# Pag3_Front_end_adc_dac.net
KiCad netlist of a schematic drawn in Altium Designer
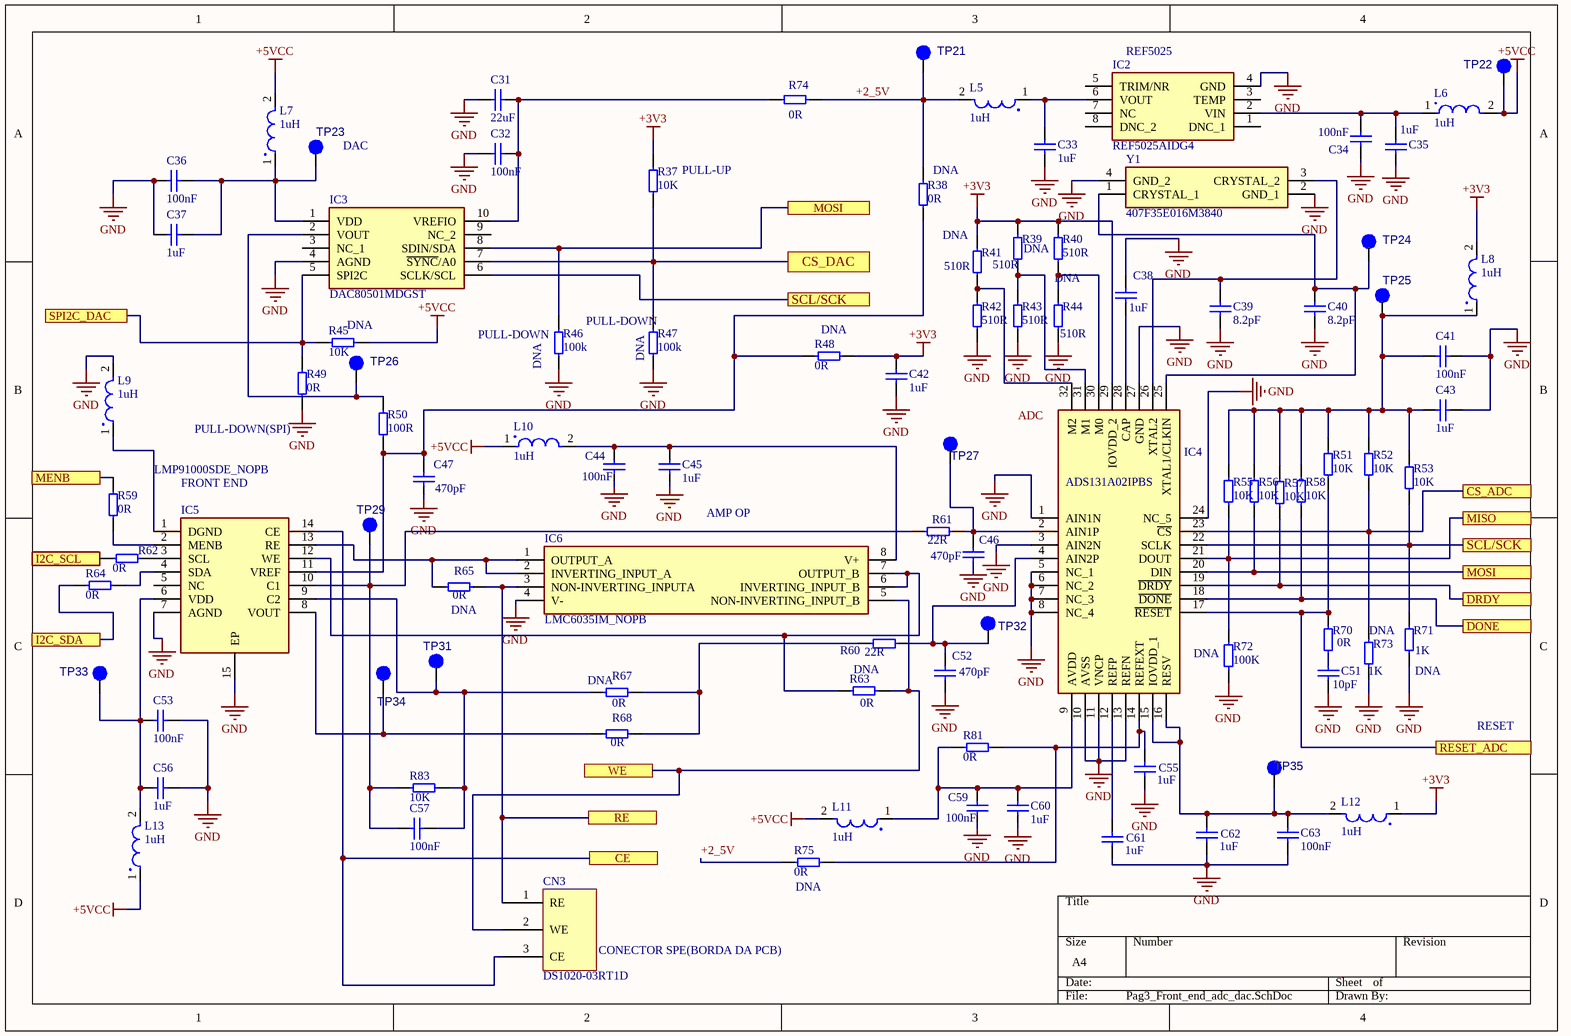
[diagram p0: Pag3_Front_end_adc_dac.SchDoc]

(export (version "E")
  (design (tool "Eeschema 10.0.6"))
  (components
    (comp (ref "C31")
      (value "22uF")
      (footprint "0603")
      (description "Multilayer Ceramic Capacitors MLCC - SMD/SMT 22uF 0603 6.3V 20%")
      (fields (field (name "MANUFACTURER") "KEMET") (field (name "MPN") "C0603C226M9PACTU"))
      (libsource (lib "potenciostato") (part "CAP_10uF_10V"))
    )
    (comp (ref "C32")
      (value "100nF")
      (footprint "0603")
      (description "Multilayer Ceramic Capacitors MLCC - SMD/SMT 100nF 16V 0603 10%")
      (fields (field (name "MPN") "C0603C104K4RACTU") (field (name "MANUFACTURER") "Kemet"))
      (libsource (lib "potenciostato") (part "Cap_1"))
    )
    (comp (ref "C33")
      (value "1uF")
      (footprint "0603")
      (description "Multilayer Ceramic Capacitors MLCC - SMD/SMT 1uF 25V 0603 10%")
      (fields
        (field (name "MANUFACTURER") "Samsung Electro-Mechanics")
        (field (name "MPN") "CL10A105KA8NNNC")
      )
      (libsource (lib "potenciostato") (part "CAP_1uF"))
    )
    (comp (ref "C34")
      (value "100nF")
      (footprint "0603")
      (description "Multilayer Ceramic Capacitors MLCC - SMD/SMT 100nF 16V 0603 10%")
      (fields (field (name "MPN") "C0603C104K4RACTU") (field (name "MANUFACTURER") "Kemet"))
      (libsource (lib "potenciostato") (part "Cap_1"))
    )
    (comp (ref "C35")
      (value "1uF")
      (footprint "0603")
      (description "Multilayer Ceramic Capacitors MLCC - SMD/SMT 1uF 25V 0603 10%")
      (fields
        (field (name "MANUFACTURER") "Samsung Electro-Mechanics")
        (field (name "MPN") "CL10A105KA8NNNC")
      )
      (libsource (lib "potenciostato") (part "CAP_1uF"))
    )
    (comp (ref "C36")
      (value "100nF")
      (footprint "0603")
      (description "Multilayer Ceramic Capacitors MLCC - SMD/SMT 100nF 16V 0603 10%")
      (fields (field (name "MPN") "C0603C104K4RACTU") (field (name "MANUFACTURER") "Kemet"))
      (libsource (lib "potenciostato") (part "Cap_1"))
    )
    (comp (ref "C37")
      (value "1uF")
      (footprint "0603")
      (description "Multilayer Ceramic Capacitors MLCC - SMD/SMT 1uF 25V 0603 10%")
      (fields
        (field (name "MANUFACTURER") "Samsung Electro-Mechanics")
        (field (name "MPN") "CL10A105KA8NNNC")
      )
      (libsource (lib "potenciostato") (part "CAP_1uF"))
    )
    (comp (ref "C38")
      (value "1uF")
      (footprint "0603")
      (description "Multilayer Ceramic Capacitors MLCC - SMD/SMT 1uF 25V 0603 10%")
      (fields
        (field (name "MANUFACTURER") "Samsung Electro-Mechanics")
        (field (name "MPN") "CL10A105KA8NNNC")
      )
      (libsource (lib "potenciostato") (part "CAP_1uF"))
    )
    (comp (ref "C39")
      (value "8.2pF")
      (footprint "0603")
      (description "Multilayer Ceramic Capacitors MLCC - SMD/SMT 8.2pF 0603 16V 0.25pF")
      (fields (field (name "MPN") "C0603C829C4GACAUTO") (field (name "MANUFACTURER") "Kemet"))
      (libsource (lib "potenciostato") (part "Cap_1_1"))
    )
    (comp (ref "C40")
      (value "8.2pF")
      (footprint "0603")
      (description "Multilayer Ceramic Capacitors MLCC - SMD/SMT 8.2pF 0603 16V 0.25pF")
      (fields (field (name "MPN") "C0603C829C4GACAUTO") (field (name "MANUFACTURER") "Kemet"))
      (libsource (lib "potenciostato") (part "Cap_1_1"))
    )
    (comp (ref "C41")
      (value "100nF")
      (footprint "0603")
      (description "Multilayer Ceramic Capacitors MLCC - SMD/SMT 100nF 16V 0603 10%")
      (fields (field (name "MPN") "C0603C104K4RACTU") (field (name "MANUFACTURER") "Kemet"))
      (libsource (lib "potenciostato") (part "Cap_1"))
    )
    (comp (ref "C42")
      (value "1uF")
      (footprint "0603")
      (description "Multilayer Ceramic Capacitors MLCC - SMD/SMT 1uF 25V 0603 10%")
      (fields
        (field (name "MANUFACTURER") "Samsung Electro-Mechanics")
        (field (name "MPN") "CL10A105KA8NNNC")
      )
      (libsource (lib "potenciostato") (part "CAP_1uF"))
    )
    (comp (ref "C43")
      (value "1uF")
      (footprint "0603")
      (description "Multilayer Ceramic Capacitors MLCC - SMD/SMT 1uF 25V 0603 10%")
      (fields
        (field (name "MANUFACTURER") "Samsung Electro-Mechanics")
        (field (name "MPN") "CL10A105KA8NNNC")
      )
      (libsource (lib "potenciostato") (part "CAP_1uF"))
    )
    (comp (ref "C44")
      (value "100nF")
      (footprint "0603")
      (description "Multilayer Ceramic Capacitors MLCC - SMD/SMT 100nF 16V 0603 10%")
      (fields (field (name "MPN") "C0603C104K4RACTU") (field (name "MANUFACTURER") "Kemet"))
      (libsource (lib "potenciostato") (part "Cap_1"))
    )
    (comp (ref "C45")
      (value "1uF")
      (footprint "0603")
      (description "Multilayer Ceramic Capacitors MLCC - SMD/SMT 1uF 25V 0603 10%")
      (fields
        (field (name "MANUFACTURER") "Samsung Electro-Mechanics")
        (field (name "MPN") "CL10A105KA8NNNC")
      )
      (libsource (lib "") (part "CAP_1uF_1"))
    )
    (comp (ref "C46")
      (value "470pF")
      (footprint "0603")
      (description "Multilayer Ceramic Capacitors MLCC - SMD/SMT 470pF 0603 25V 5%")
      (fields (field (name "MANUFACTURER") "Kyocera AVX") (field (name "MPN") "06033A471JAT2A"))
      (libsource (lib "potenciostato") (part "CAP_100nF_10V"))
    )
    (comp (ref "C47")
      (value "470pF")
      (footprint "0603")
      (description "Multilayer Ceramic Capacitors MLCC - SMD/SMT 470pF 0603 25V 5%")
      (fields (field (name "MANUFACTURER") "Kyocera AVX") (field (name "MPN") "06033A471JAT2A"))
      (libsource (lib "potenciostato") (part "CAP_100nF_10V"))
    )
    (comp (ref "C51")
      (value "10pF")
      (footprint "0603")
      (description "Multilayer Ceramic Capacitors MLCC - SMD/SMT 10pF 0603 16V 10%")
      (fields (field (name "MPN") "0603YD100KAT2A") (field (name "MANUFACTURER") "Kyocera AVX"))
      (libsource (lib "potenciostato") (part "Cap_1_1"))
    )
    (comp (ref "C52")
      (value "470pF")
      (footprint "0603")
      (description "Multilayer Ceramic Capacitors MLCC - SMD/SMT 470pF 0603 25V 5%")
      (fields (field (name "MANUFACTURER") "Kyocera AVX") (field (name "MPN") "06033A471JAT2A"))
      (libsource (lib "potenciostato") (part "CAP_100nF_10V"))
    )
    (comp (ref "C53")
      (value "100nF")
      (footprint "0603")
      (description "Multilayer Ceramic Capacitors MLCC - SMD/SMT 100nF 16V 0603 10%")
      (fields (field (name "MPN") "C0603C104K4RACTU") (field (name "MANUFACTURER") "Kemet"))
      (libsource (lib "potenciostato") (part "Cap_1"))
    )
    (comp (ref "C55")
      (value "1uF")
      (footprint "0603")
      (description "Multilayer Ceramic Capacitors MLCC - SMD/SMT 1uF 25V 0603 10%")
      (fields
        (field (name "MANUFACTURER") "Samsung Electro-Mechanics")
        (field (name "MPN") "CL10A105KA8NNNC")
      )
      (libsource (lib "potenciostato") (part "CAP_1uF"))
    )
    (comp (ref "C56")
      (value "1uF")
      (footprint "0603")
      (description "Multilayer Ceramic Capacitors MLCC - SMD/SMT 1uF 25V 0603 10%")
      (fields
        (field (name "MANUFACTURER") "Samsung Electro-Mechanics")
        (field (name "MPN") "CL10A105KA8NNNC")
      )
      (libsource (lib "potenciostato") (part "CAP_1uF"))
    )
    (comp (ref "C57")
      (value "100nF")
      (footprint "0603")
      (description "Multilayer Ceramic Capacitors MLCC - SMD/SMT 100nF 16V 0603 10%")
      (fields (field (name "MPN") "C0603C104K4RACTU") (field (name "MANUFACTURER") "Kemet"))
      (libsource (lib "potenciostato") (part "Cap_1"))
    )
    (comp (ref "C59")
      (value "100nF")
      (footprint "0603")
      (description "Multilayer Ceramic Capacitors MLCC - SMD/SMT 100nF 16V 0603 10%")
      (fields (field (name "MPN") "C0603C104K4RACTU") (field (name "MANUFACTURER") "Kemet"))
      (libsource (lib "potenciostato") (part "Cap_1"))
    )
    (comp (ref "C60")
      (value "1uF")
      (footprint "0603")
      (description "Multilayer Ceramic Capacitors MLCC - SMD/SMT 1uF 25V 0603 10%")
      (fields
        (field (name "MANUFACTURER") "Samsung Electro-Mechanics")
        (field (name "MPN") "CL10A105KA8NNNC")
      )
      (libsource (lib "potenciostato") (part "CAP_1uF"))
    )
    (comp (ref "C61")
      (value "1uF")
      (footprint "0603")
      (description "Multilayer Ceramic Capacitors MLCC - SMD/SMT 1uF 25V 0603 10%")
      (fields
        (field (name "MANUFACTURER") "Samsung Electro-Mechanics")
        (field (name "MPN") "CL10A105KA8NNNC")
      )
      (libsource (lib "potenciostato") (part "CAP_1uF"))
    )
    (comp (ref "C62")
      (value "1uF")
      (footprint "0603")
      (description "Multilayer Ceramic Capacitors MLCC - SMD/SMT 1uF 25V 0603 10%")
      (fields
        (field (name "MANUFACTURER") "Samsung Electro-Mechanics")
        (field (name "MPN") "CL10A105KA8NNNC")
      )
      (libsource (lib "potenciostato") (part "CAP_1uF"))
    )
    (comp (ref "C63")
      (value "100nF")
      (footprint "0603")
      (description "Multilayer Ceramic Capacitors MLCC - SMD/SMT 100nF 16V 0603 10%")
      (fields (field (name "MPN") "C0603C104K4RACTU") (field (name "MANUFACTURER") "Kemet"))
      (libsource (lib "potenciostato") (part "Cap_1"))
    )
    (comp (ref "CN3")
      (value "DS1020-03RT1D")
      (footprint "DS1020-03RT1D")
      (description "Connector: FFC/FPC; angled 90°; PIN: 3; Non-ZIF; THT; tinned; 20mΩ")
      (fields (field (name "MANUFACTURER") "Connfly"))
      (libsource (lib "DS1020-03RT1D") (part "DS1020-03RT1D"))
    )
    (comp (ref "IC2")
      (value "REF5025AIDG4")
      (footprint "SOIC127P600X175-8N")
      (description "Integrated Circuit")
      (fields (field (name "MANUFACTURER") "Texas Instruments"))
      (libsource (lib "ref5025") (part "REF5025AIDG4"))
    )
    (comp (ref "IC3")
      (value "DAC80501MDGST")
      (footprint "SOP50P490X110-10N")
      (description "Integrated Circuit")
      (fields (field (name "MANUFACTURER") "Texas Instruments"))
      (libsource (lib "dac80501") (part "DAC80501MDGST"))
    )
    (comp (ref "IC4")
      (value "ADS131A02IPBS")
      (footprint "QFP50P700X700X120-32N")
      (description "Integrated Circuit")
      (fields (field (name "MANUFACTURER") "Texas Instruments"))
      (libsource (lib "ADS131A02") (part "ADS131A02IPBS"))
    )
    (comp (ref "IC5")
      (value "LMP91000SDE_NOPB")
      (footprint "SON50P400X400X80-15N")
      (description "Integrated Circuit")
      (fields (field (name "MPN") "LMP91000SDE/NOPB") (field (name "MANUFACTURER") "Texas Instruments"))
      (libsource (lib "LMP91000") (part "LMP91000SDE_NOPB"))
    )
    (comp (ref "IC6")
      (value "LMC6035IM_NOPB")
      (footprint "SOIC127P600X175-8N")
      (description "Integrated Circuit")
      (fields (field (name "MANUFACTURER") "Texas Instruments") (field (name "MPN") "LMC6035IM/NOPB"))
      (libsource (lib "*") (part "LMC6035IM_NOPB"))
    )
    (comp (ref "L5")
      (value "1uH")
      (footprint "SRP4012TA")
      (description "Power Inductors - SMD 1uH 20% SMD 4012 AEC-Q200")
      (fields (field (name "MANUFACTURER") "Bourns") (field (name "MPN") "SRP4012TA-1R0M"))
      (libsource (lib "potenciostato") (part "IC_1uH"))
    )
    (comp (ref "L6")
      (value "1uH")
      (footprint "SRP4012TA")
      (description "Power Inductors - SMD 1uH 20% SMD 4012 AEC-Q200")
      (fields (field (name "MANUFACTURER") "Bourns") (field (name "MPN") "SRP4012TA-1R0M"))
      (libsource (lib "potenciostato") (part "IC_1uH"))
    )
    (comp (ref "L7")
      (value "1uH")
      (footprint "SRP4012TA")
      (description "Power Inductors - SMD 1uH 20% SMD 4012 AEC-Q200")
      (fields (field (name "MANUFACTURER") "Bourns") (field (name "MPN") "SRP4012TA-1R0M"))
      (libsource (lib "potenciostato") (part "IC_1uH"))
    )
    (comp (ref "L8")
      (value "1uH")
      (footprint "SRP4012TA")
      (description "Power Inductors - SMD 1uH 20% SMD 4012 AEC-Q200")
      (fields (field (name "MANUFACTURER") "Bourns") (field (name "MPN") "SRP4012TA-1R0M"))
      (libsource (lib "potenciostato") (part "IC_1uH"))
    )
    (comp (ref "L9")
      (value "1uH")
      (footprint "SRP4012TA")
      (description "Power Inductors - SMD 1uH 20% SMD 4012 AEC-Q200")
      (fields (field (name "MANUFACTURER") "Bourns") (field (name "MPN") "SRP4012TA-1R0M"))
      (libsource (lib "potenciostato") (part "IC_1uH"))
    )
    (comp (ref "L10")
      (value "1uH")
      (footprint "SRP4012TA")
      (description "Power Inductors - SMD 1uH 20% SMD 4012 AEC-Q200")
      (fields (field (name "MANUFACTURER") "Bourns") (field (name "MPN") "SRP4012TA-1R0M"))
      (libsource (lib "potenciostato") (part "IC_1uH"))
    )
    (comp (ref "L11")
      (value "1uH")
      (footprint "SRP4012TA")
      (description "Power Inductors - SMD 1uH 20% SMD 4012 AEC-Q200")
      (fields (field (name "MANUFACTURER") "Bourns") (field (name "MPN") "SRP4012TA-1R0M"))
      (libsource (lib "potenciostato") (part "IC_1uH"))
    )
    (comp (ref "L12")
      (value "1uH")
      (footprint "SRP4012TA")
      (description "Power Inductors - SMD 1uH 20% SMD 4012 AEC-Q200")
      (fields (field (name "MANUFACTURER") "Bourns") (field (name "MPN") "SRP4012TA-1R0M"))
      (libsource (lib "potenciostato") (part "IC_1uH"))
    )
    (comp (ref "L13")
      (value "1uH")
      (footprint "SRP4012TA")
      (description "Power Inductors - SMD 1uH 20% SMD 4012 AEC-Q200")
      (fields (field (name "MANUFACTURER") "Bourns") (field (name "MPN") "SRP4012TA-1R0M"))
      (libsource (lib "potenciostato") (part "IC_1uH"))
    )
    (comp (ref "R37")
      (value "10K")
      (footprint "0603")
      (description "Thick Film Resistors - SMD 10 kOhms 100-200 mW 0603 1%")
      (fields (field (name "MPN") "RC0603FR-1310KL") (field (name "MANUFACTURER") "Yageo"))
      (libsource (lib "potenciostato") (part "Pullup_Res_100K_0603_RES"))
    )
    (comp (ref "R38")
      (value "0R")
      (footprint "0603")
      (description "Thick Film Resistors - SMD 0 Ohms 100 mW 0603 5%")
      (fields
        (field (name "MPN") "RC0603JR-070RL")
        (field (name "MANUFACTURER") "Yageo")
        (field (name "PCBA") "DNA")
      )
      (libsource (lib "potenciostato") (part "Pullup_Res_100K_0603_RES"))
    )
    (comp (ref "R39")
      (value "510R")
      (footprint "0603")
      (description "Thick Film Resistors - SMD 510 Ohms 0603 100mW 1%")
      (fields
        (field (name "MPN") "RC0603FR-13510RL")
        (field (name "MANUFACTURER") "Yageo")
        (field (name "PCBA") "DNA")
      )
      (libsource (lib "") (part "Pullup_Res_0_0603_RES_1"))
    )
    (comp (ref "R40")
      (value "510R")
      (footprint "0603")
      (description "Thick Film Resistors - SMD 510 Ohms 0603 100mW 1%")
      (fields (field (name "MPN") "RC0603FR-13510RL") (field (name "MANUFACTURER") "Yageo"))
      (libsource (lib "") (part "Pullup_Res_0_0603_RES_1"))
    )
    (comp (ref "R41")
      (value "510R")
      (footprint "0603")
      (description "Thick Film Resistors - SMD 510 Ohms 0603 100mW 1%")
      (fields
        (field (name "MPN") "RC0603FR-13510RL")
        (field (name "MANUFACTURER") "Yageo")
        (field (name "PCBA") "DNA")
      )
      (libsource (lib "") (part "Pullup_Res_0_0603_RES_1"))
    )
    (comp (ref "R42")
      (value "510R")
      (footprint "0603")
      (description "Thick Film Resistors - SMD 510 Ohms 0603 100mW 1%")
      (fields (field (name "MPN") "RC0603FR-13510RL") (field (name "MANUFACTURER") "Yageo"))
      (libsource (lib "") (part "Pullup_Res_0_0603_RES_1"))
    )
    (comp (ref "R43")
      (value "510R")
      (footprint "0603")
      (description "Thick Film Resistors - SMD 510 Ohms 0603 100mW 1%")
      (fields (field (name "MPN") "RC0603FR-13510RL") (field (name "MANUFACTURER") "Yageo"))
      (libsource (lib "") (part "Pullup_Res_0_0603_RES_1"))
    )
    (comp (ref "R44")
      (value "510R")
      (footprint "0603")
      (description "Thick Film Resistors - SMD 510 Ohms 0603 100mW 1%")
      (fields
        (field (name "MPN") "RC0603FR-13510RL")
        (field (name "MANUFACTURER") "Yageo")
        (field (name "PCBA") "DNA")
      )
      (libsource (lib "") (part "Pullup_Res_0_0603_RES_1"))
    )
    (comp (ref "R45")
      (value "10K")
      (footprint "0603")
      (description "Thick Film Resistors - SMD 10 kOhms 100-200 mW 0603 1%")
      (fields
        (field (name "MPN") "RC0603FR-1310KL")
        (field (name "MANUFACTURER") "Yageo")
        (field (name "PCBA") "DNA")
      )
      (libsource (lib "") (part "Pullup_Res_100K_0603_RES_1"))
    )
    (comp (ref "R46")
      (value "100k")
      (footprint "0603")
      (description "Thick Film Resistors - SMD 100 kOhms 0603 100mW 1%")
      (fields (field (name "MPN") "RC0603FR-07100KL") (field (name "MANUFACTURER") "Yageo"))
      (libsource (lib "potenciostato") (part "Pullup_Res_100K_0603_RES"))
    )
    (comp (ref "R47")
      (value "100k")
      (footprint "0603")
      (description "Thick Film Resistors - SMD 100 kOhms 0603 100mW 1%")
      (fields (field (name "MPN") "RC0603FR-07100KL") (field (name "MANUFACTURER") "Yageo"))
      (libsource (lib "potenciostato") (part "Pullup_Res_100K_0603_RES"))
    )
    (comp (ref "R48")
      (value "0R")
      (footprint "0603")
      (description "Thick Film Resistors - SMD 0 Ohms 100 mW 0603 5%")
      (fields
        (field (name "MPN") "RC0603JR-070RL")
        (field (name "MANUFACTURER") "Yageo")
        (field (name "PCBA") "DNA")
      )
      (libsource (lib "") (part "Pullup_Res_100K_0603_RES_2"))
    )
    (comp (ref "R49")
      (value "0R")
      (footprint "0603")
      (description "Thick Film Resistors - SMD 0 Ohms 100 mW 0603 5%")
      (fields (field (name "MPN") "RC0603JR-070RL") (field (name "MANUFACTURER") "Yageo"))
      (libsource (lib "") (part "Pullup_Res_0_0603_RES_1"))
    )
    (comp (ref "R50")
      (value "100R")
      (footprint "0603")
      (description "Thick Film Resistors - SMD 100 Ohms 0603 100mW 1%")
      (fields (field (name "MPN") "ERJ-3EKF1000V") (field (name "MANUFACTURER") "Panasonic"))
      (libsource (lib "") (part "Pullup_Res_0_0603_RES_1"))
    )
    (comp (ref "R51")
      (value "10K")
      (footprint "0603")
      (description "Thick Film Resistors - SMD 10 kOhms 100-200 mW 0603 1%")
      (fields (field (name "MPN") "RC0603FR-1310KL") (field (name "MANUFACTURER") "Yageo"))
      (libsource (lib "potenciostato") (part "Pullup_Res_100K_0603_RES"))
    )
    (comp (ref "R52")
      (value "10K")
      (footprint "0603")
      (description "Thick Film Resistors - SMD 10 kOhms 100-200 mW 0603 1%")
      (fields (field (name "MPN") "RC0603FR-1310KL") (field (name "MANUFACTURER") "Yageo"))
      (libsource (lib "potenciostato") (part "Pullup_Res_100K_0603_RES"))
    )
    (comp (ref "R53")
      (value "10K")
      (footprint "0603")
      (description "Thick Film Resistors - SMD 10 kOhms 100-200 mW 0603 1%")
      (fields (field (name "MPN") "RC0603FR-1310KL") (field (name "MANUFACTURER") "Yageo"))
      (libsource (lib "potenciostato") (part "Pullup_Res_100K_0603_RES"))
    )
    (comp (ref "R55")
      (value "10K")
      (footprint "0603")
      (description "Thick Film Resistors - SMD 10 kOhms 100-200 mW 0603 1%")
      (fields (field (name "MPN") "RC0603FR-1310KL") (field (name "MANUFACTURER") "Yageo"))
      (libsource (lib "potenciostato") (part "Pullup_Res_100K_0603_RES"))
    )
    (comp (ref "R56")
      (value "10K")
      (footprint "0603")
      (description "Thick Film Resistors - SMD 10 kOhms 100-200 mW 0603 1%")
      (fields (field (name "MPN") "RC0603FR-1310KL") (field (name "MANUFACTURER") "Yageo"))
      (libsource (lib "potenciostato") (part "Pullup_Res_100K_0603_RES"))
    )
    (comp (ref "R57")
      (value "10K")
      (footprint "0603")
      (description "Thick Film Resistors - SMD 10 kOhms 100-200 mW 0603 1%")
      (fields (field (name "MPN") "RC0603FR-1310KL") (field (name "MANUFACTURER") "Yageo"))
      (libsource (lib "potenciostato") (part "Pullup_Res_100K_0603_RES"))
    )
    (comp (ref "R58")
      (value "10K")
      (footprint "0603")
      (description "Thick Film Resistors - SMD 10 kOhms 100-200 mW 0603 1%")
      (fields (field (name "MPN") "RC0603FR-1310KL") (field (name "MANUFACTURER") "Yageo"))
      (libsource (lib "potenciostato") (part "Pullup_Res_100K_0603_RES"))
    )
    (comp (ref "R59")
      (value "0R")
      (footprint "0603")
      (description "Thick Film Resistors - SMD 0 Ohms 100 mW 0603 5%")
      (fields (field (name "MPN") "RC0603JR-070RL") (field (name "MANUFACTURER") "Yageo"))
      (libsource (lib "") (part "Pullup_Res_0_0603_RES_1"))
    )
    (comp (ref "R60")
      (value "22R")
      (footprint "0603")
      (description "Thin Film Resistors - SMD 22Ohms 0603 100mW 1%")
      (fields (field (name "MPN") "RT0603FRE0722RL") (field (name "MANUFACTURER") "Yageo"))
      (libsource (lib "potenciostato") (part "Res_3"))
    )
    (comp (ref "R61")
      (value "22R")
      (footprint "0603")
      (description "Thin Film Resistors - SMD 22Ohms 0603 100mW 1%")
      (fields (field (name "MPN") "RT0603FRE0722RL") (field (name "MANUFACTURER") "Yageo"))
      (libsource (lib "potenciostato") (part "Res_3"))
    )
    (comp (ref "R62")
      (value "0R")
      (footprint "0603")
      (description "Thick Film Resistors - SMD 0 Ohms 100 mW 0603 5%")
      (fields (field (name "MPN") "RC0603JR-070RL") (field (name "MANUFACTURER") "Yageo"))
      (libsource (lib "potenciostato") (part "Pullup_Res_0_0603_RES"))
    )
    (comp (ref "R63")
      (value "0R")
      (footprint "0603")
      (description "Thick Film Resistors - SMD 0 Ohms 100 mW 0603 5%")
      (fields
        (field (name "MPN") "RC0603JR-070RL")
        (field (name "MANUFACTURER") "Yageo")
        (field (name "PCBA") "DNA")
      )
      (libsource (lib "potenciostato") (part "Pullup_Res_0_0603_RES"))
    )
    (comp (ref "R64")
      (value "0R")
      (footprint "0603")
      (description "Thick Film Resistors - SMD 0 Ohms 100 mW 0603 5%")
      (fields (field (name "MPN") "RC0603JR-070RL") (field (name "MANUFACTURER") "Yageo"))
      (libsource (lib "potenciostato") (part "Pullup_Res_0_0603_RES"))
    )
    (comp (ref "R65")
      (value "0R")
      (footprint "0603")
      (description "Thick Film Resistors - SMD 0 Ohms 100 mW 0603 5%")
      (fields
        (field (name "MPN") "RC0603JR-070RL")
        (field (name "MANUFACTURER") "Yageo")
        (field (name "PCBA") "DNA")
      )
      (libsource (lib "potenciostato") (part "Pullup_Res_0_0603_RES"))
    )
    (comp (ref "R67")
      (value "0R")
      (footprint "0603")
      (description "Thick Film Resistors - SMD 0 Ohms 100 mW 0603 5%")
      (fields
        (field (name "MPN") "RC0603JR-070RL")
        (field (name "MANUFACTURER") "Yageo")
        (field (name "PCBA") "DNA")
      )
      (libsource (lib "potenciostato") (part "Pullup_Res_0_0603_RES"))
    )
    (comp (ref "R68")
      (value "0R")
      (footprint "0603")
      (description "Thick Film Resistors - SMD 0 Ohms 100 mW 0603 5%")
      (fields (field (name "MPN") "RC0603JR-070RL") (field (name "MANUFACTURER") "Yageo"))
      (libsource (lib "potenciostato") (part "Pullup_Res_0_0603_RES"))
    )
    (comp (ref "R70")
      (value "0R")
      (footprint "0603")
      (description "Thick Film Resistors - SMD 0 Ohms 100 mW 0603 5%")
      (fields (field (name "MPN") "RC0603JR-070RL") (field (name "MANUFACTURER") "Yageo"))
      (libsource (lib "") (part "Pullup_Res_0_0603_RES_1"))
    )
    (comp (ref "R71")
      (value "1K")
      (footprint "0603")
      (description "Thick Film Resistors - SMD 1 kOhms 100 mW 0603 5%")
      (fields
        (field (name "MANUFACTURER") "Yageo")
        (field (name "MPN") "RC0603JR-071KL")
        (field (name "PCBA") "DNA")
      )
      (libsource (lib "potenciostato") (part "Res"))
    )
    (comp (ref "R72")
      (value "100K")
      (footprint "0603")
      (description "Thick Film Resistors - SMD 100 kOhms 0603 100mW 1%")
      (fields
        (field (name "MPN") "RC0603FR-07100KL")
        (field (name "MANUFACTURER") "Yageo")
        (field (name "PCBA") "DNA")
      )
      (libsource (lib "potenciostato") (part "Pullup_Res_100K_0603_RES"))
    )
    (comp (ref "R73")
      (value "1K")
      (footprint "0603")
      (description "Thick Film Resistors - SMD 1 kOhms 100 mW 0603 5%")
      (fields
        (field (name "MANUFACTURER") "Yageo")
        (field (name "MPN") "RC0603JR-071KL")
        (field (name "PCBA") "DNA")
      )
      (libsource (lib "potenciostato") (part "Res"))
    )
    (comp (ref "R74")
      (value "0R")
      (footprint "0603")
      (description "Thick Film Resistors - SMD 0 Ohms 100 mW 0603 5%")
      (fields (field (name "MPN") "RC0603JR-070RL") (field (name "MANUFACTURER") "Yageo"))
      (libsource (lib "potenciostato") (part "Pullup_Res_0_0603_RES"))
    )
    (comp (ref "R75")
      (value "0R")
      (footprint "0603")
      (description "Thick Film Resistors - SMD 0 Ohms 100 mW 0603 5%")
      (fields
        (field (name "MPN") "RC0603JR-070RL")
        (field (name "MANUFACTURER") "Yageo")
        (field (name "PCBA") "DNA")
      )
      (libsource (lib "potenciostato") (part "Pullup_Res_0_0603_RES"))
    )
    (comp (ref "R81")
      (value "0R")
      (footprint "0603")
      (description "Thick Film Resistors - SMD 0 Ohms 100 mW 0603 5%")
      (fields (field (name "MPN") "RC0603JR-070RL") (field (name "MANUFACTURER") "Yageo"))
      (libsource (lib "potenciostato") (part "Pullup_Res_0_0603_RES"))
    )
    (comp (ref "R83")
      (value "10K")
      (footprint "0603")
      (description "Thick Film Resistors - SMD 10 kOhms 100-200 mW 0603 1%")
      (fields (field (name "MPN") "RC0603FR-1310KL") (field (name "MANUFACTURER") "Yageo"))
      (libsource (lib "") (part "Pullup_Res_100K_0603_RES_1"))
    )
    (comp (ref "TP21")
      (value "Test Point")
      (footprint "TEST")
      (fields (field (name "MPN") "Test_Point") (field (name "MANUFACTURER") "DNA"))
      (libsource (lib "potenciostato") (part "TESTPOINT"))
    )
    (comp (ref "TP22")
      (value "Test Point")
      (footprint "TEST")
      (fields (field (name "MPN") "Test_Point") (field (name "MANUFACTURER") "DNA"))
      (libsource (lib "potenciostato") (part "TESTPOINT"))
    )
    (comp (ref "TP23")
      (value "Test Point")
      (footprint "TEST")
      (fields (field (name "MPN") "Test_Point") (field (name "MANUFACTURER") "DNA"))
      (libsource (lib "potenciostato") (part "TESTPOINT"))
    )
    (comp (ref "TP24")
      (value "Test Point")
      (footprint "TEST")
      (fields (field (name "MPN") "Test_Point") (field (name "MANUFACTURER") "DNA"))
      (libsource (lib "potenciostato") (part "TESTPOINT"))
    )
    (comp (ref "TP25")
      (value "Test Point")
      (footprint "TEST")
      (fields (field (name "MPN") "Test_Point") (field (name "MANUFACTURER") "DNA"))
      (libsource (lib "potenciostato") (part "TESTPOINT"))
    )
    (comp (ref "TP26")
      (value "Test Point")
      (footprint "TEST")
      (fields (field (name "MPN") "Test_Point") (field (name "MANUFACTURER") "DNA"))
      (libsource (lib "potenciostato") (part "TESTPOINT"))
    )
    (comp (ref "TP27")
      (value "Test Point")
      (footprint "TEST")
      (fields (field (name "MPN") "Test_Point") (field (name "MANUFACTURER") "DNA"))
      (libsource (lib "potenciostato") (part "TESTPOINT"))
    )
    (comp (ref "TP29")
      (value "Test Point")
      (footprint "TEST")
      (fields (field (name "MPN") "Test_Point") (field (name "MANUFACTURER") "DNA"))
      (libsource (lib "potenciostato") (part "TESTPOINT"))
    )
    (comp (ref "TP31")
      (value "Test Point")
      (footprint "TEST")
      (fields (field (name "MPN") "Test_Point") (field (name "MANUFACTURER") "DNA"))
      (libsource (lib "potenciostato") (part "TESTPOINT"))
    )
    (comp (ref "TP32")
      (value "Test Point")
      (footprint "TEST")
      (fields (field (name "MPN") "Test_Point") (field (name "MANUFACTURER") "DNA"))
      (libsource (lib "potenciostato") (part "TESTPOINT"))
    )
    (comp (ref "TP33")
      (value "Test Point")
      (footprint "TEST")
      (fields (field (name "MPN") "Test_Point") (field (name "MANUFACTURER") "DNA"))
      (libsource (lib "potenciostato") (part "TESTPOINT"))
    )
    (comp (ref "TP34")
      (value "Test Point")
      (footprint "TEST")
      (fields (field (name "MPN") "Test_Point") (field (name "MANUFACTURER") "DNA"))
      (libsource (lib "potenciostato") (part "TESTPOINT"))
    )
    (comp (ref "TP35")
      (value "Test Point")
      (footprint "TEST")
      (fields (field (name "MPN") "Test_Point") (field (name "MANUFACTURER") "DNA"))
      (libsource (lib "potenciostato") (part "TESTPOINT"))
    )
    (comp (ref "Y1")
      (value "407F35E016M3840")
      (footprint "SamacSys:407F35E016M3840")
      (description "Crystal or Oscillator")
      (fields (field (name "MANUFACTURER") "CTS Electronic Components"))
      (libsource (lib "*") (part "407F35E016M3840"))
    )
  )
  (nets
    (net (code "1") (name "+3V3") (class "Default")
      (node (ref "C42") (pin "2") (pinfunction "2_2") (pintype "passive"))
      (node (ref "IC4") (pin "29") (pinfunction "IOVDD_2_29") (pintype "passive"))
      (node (ref "L12") (pin "1") (pinfunction "1_1") (pintype "passive"))
      (node (ref "L8") (pin "2") (pinfunction "2_2") (pintype "passive"))
      (node (ref "R37") (pin "2") (pinfunction "2_2") (pintype "passive"))
      (node (ref "R39") (pin "2") (pinfunction "2_2") (pintype "passive"))
      (node (ref "R40") (pin "2") (pinfunction "2_2") (pintype "passive"))
      (node (ref "R41") (pin "2") (pinfunction "2_2") (pintype "passive"))
      (node (ref "R48") (pin "2") (pinfunction "2_2") (pintype "passive"))
    )
    (net (code "2") (name "+5VCC") (class "Default")
      (node (ref "L10") (pin "1") (pinfunction "1_1") (pintype "passive"))
      (node (ref "L11") (pin "2") (pinfunction "2_2") (pintype "passive"))
      (node (ref "L13") (pin "1") (pinfunction "1_1") (pintype "passive"))
      (node (ref "L6") (pin "2") (pinfunction "2_2") (pintype "passive"))
      (node (ref "L7") (pin "2") (pinfunction "2_2") (pintype "passive"))
      (node (ref "R45") (pin "1") (pinfunction "1_1") (pintype "passive"))
      (node (ref "TP22") (pin "1") (pinfunction "TP_1") (pintype "passive"))
    )
    (net (code "3") (name "/+2_5V") (class "Default")
      (node (ref "L5") (pin "2") (pinfunction "2_2") (pintype "passive"))
      (node (ref "R38") (pin "2") (pinfunction "2_2") (pintype "passive"))
      (node (ref "R74") (pin "1") (pinfunction "1_1") (pintype "passive"))
      (node (ref "R75") (pin "2") (pinfunction "2_2") (pintype "passive"))
      (node (ref "TP21") (pin "1") (pinfunction "TP_1") (pintype "passive"))
    )
    (net (code "6") (name "/CE") (class "Default")
      (node (ref "CN3") (pin "3") (pinfunction "CE_3") (pintype "passive"))
      (node (ref "IC5") (pin "14") (pinfunction "CE_14") (pintype "passive"))
    )
    (net (code "7") (name "/CS_ADC") (class "Default")
      (node (ref "IC4") (pin "23") (pinfunction "~{CS}_23") (pintype "passive"))
      (node (ref "R52") (pin "1") (pinfunction "1_1") (pintype "passive"))
      (node (ref "R73") (pin "2") (pinfunction "2_2") (pintype "passive"))
    )
    (net (code "8") (name "/CS_DAC") (class "Default")
      (node (ref "IC3") (pin "7") (pinfunction "~{SYNC}/A0_7") (pintype "passive"))
      (node (ref "R37") (pin "1") (pinfunction "1_1") (pintype "passive"))
      (node (ref "R47") (pin "2") (pinfunction "2_2") (pintype "passive"))
    )
    (net (code "9") (name "/DONE") (class "Default")
      (node (ref "IC4") (pin "18") (pinfunction "~{DONE}_18") (pintype "passive"))
      (node (ref "R58") (pin "1") (pinfunction "1_1") (pintype "passive"))
    )
    (net (code "10") (name "/DRDY") (class "Default")
      (node (ref "IC4") (pin "19") (pinfunction "~{DRDY}_19") (pintype "passive"))
      (node (ref "R57") (pin "1") (pinfunction "1_1") (pintype "passive"))
    )
    (net (code "11") (name "/I2C_SCL") (class "Default")
      (node (ref "R62") (pin "2") (pinfunction "2_2") (pintype "passive"))
    )
    (net (code "12") (name "/I2C_SDA") (class "Default")
      (node (ref "R64") (pin "2") (pinfunction "2_2") (pintype "passive"))
    )
    (net (code "13") (name "/MENB") (class "Default")
      (node (ref "R59") (pin "2") (pinfunction "2_2") (pintype "passive"))
    )
    (net (code "14") (name "/MISO") (class "Default")
      (node (ref "IC4") (pin "21") (pinfunction "DOUT_21") (pintype "passive"))
      (node (ref "R55") (pin "1") (pinfunction "1_1") (pintype "passive"))
      (node (ref "R72") (pin "2") (pinfunction "2_2") (pintype "passive"))
    )
    (net (code "15") (name "/MOSI") (class "Default")
      (node (ref "IC3") (pin "8") (pinfunction "SDIN/SDA_8") (pintype "passive"))
      (node (ref "IC4") (pin "20") (pinfunction "DIN_20") (pintype "passive"))
      (node (ref "R46") (pin "2") (pinfunction "2_2") (pintype "passive"))
      (node (ref "R56") (pin "1") (pinfunction "1_1") (pintype "passive"))
    )
    (net (code "16") (name "/RE") (class "Default")
      (node (ref "CN3") (pin "1") (pinfunction "RE_1") (pintype "passive"))
      (node (ref "IC6") (pin "3") (pinfunction "NON-INVERTING_INPUTA_3") (pintype "passive"))
      (node (ref "R65") (pin "1") (pinfunction "1_1") (pintype "passive"))
    )
    (net (code "17") (name "/RESET_ADC") (class "Default")
      (node (ref "IC4") (pin "17") (pinfunction "~{RESET}_17") (pintype "passive"))
      (node (ref "R51") (pin "1") (pinfunction "1_1") (pintype "passive"))
      (node (ref "R70") (pin "2") (pinfunction "2_2") (pintype "passive"))
    )
    (net (code "18") (name "/SCL{slash}SCK") (class "Default")
      (node (ref "IC3") (pin "6") (pinfunction "SCLK/SCL_6") (pintype "passive"))
      (node (ref "IC4") (pin "22") (pinfunction "SCLK_22") (pintype "passive"))
      (node (ref "R53") (pin "1") (pinfunction "1_1") (pintype "passive"))
      (node (ref "R71") (pin "2") (pinfunction "2_2") (pintype "passive"))
    )
    (net (code "19") (name "/SPI2C_DAC") (class "Default")
      (node (ref "IC3") (pin "5") (pinfunction "SPI2C_5") (pintype "passive"))
      (node (ref "R45") (pin "2") (pinfunction "2_2") (pintype "passive"))
      (node (ref "R49") (pin "2") (pinfunction "2_2") (pintype "passive"))
    )
    (net (code "20") (name "/WE") (class "Default")
      (node (ref "CN3") (pin "2") (pinfunction "WE_2") (pintype "passive"))
      (node (ref "IC6") (pin "5") (pinfunction "NON-INVERTING_INPUT_B_5") (pintype "passive"))
      (node (ref "R63") (pin "1") (pinfunction "1_1") (pintype "passive"))
    )
    (net (code "21") (name "GND") (class "Default")
      (node (ref "C31") (pin "1") (pinfunction "1_1") (pintype "passive"))
      (node (ref "C32") (pin "2") (pinfunction "2_2") (pintype "passive"))
      (node (ref "C33") (pin "1") (pinfunction "1_1") (pintype "passive"))
      (node (ref "C34") (pin "1") (pinfunction "1_1") (pintype "passive"))
      (node (ref "C35") (pin "1") (pinfunction "1_1") (pintype "passive"))
      (node (ref "C36") (pin "1") (pinfunction "1_1") (pintype "passive"))
      (node (ref "C37") (pin "2") (pinfunction "2_2") (pintype "passive"))
      (node (ref "C38") (pin "2") (pinfunction "2_2") (pintype "passive"))
      (node (ref "C39") (pin "1") (pinfunction "1_1") (pintype "passive"))
      (node (ref "C40") (pin "1") (pinfunction "1_1") (pintype "passive"))
      (node (ref "C41") (pin "2") (pinfunction "2_2") (pintype "passive"))
      (node (ref "C42") (pin "1") (pinfunction "1_1") (pintype "passive"))
      (node (ref "C43") (pin "1") (pinfunction "1_1") (pintype "passive"))
      (node (ref "C44") (pin "1") (pinfunction "1_1") (pintype "passive"))
      (node (ref "C45") (pin "2") (pinfunction "2_2") (pintype "passive"))
      (node (ref "C46") (pin "1") (pinfunction "1_1") (pintype "passive"))
      (node (ref "C47") (pin "1") (pinfunction "1_1") (pintype "passive"))
      (node (ref "C51") (pin "1") (pinfunction "1_1") (pintype "passive"))
      (node (ref "C52") (pin "1") (pinfunction "1_1") (pintype "passive"))
      (node (ref "C53") (pin "2") (pinfunction "2_2") (pintype "passive"))
      (node (ref "C55") (pin "1") (pinfunction "1_1") (pintype "passive"))
      (node (ref "C56") (pin "1") (pinfunction "1_1") (pintype "passive"))
      (node (ref "C59") (pin "1") (pinfunction "1_1") (pintype "passive"))
      (node (ref "C60") (pin "1") (pinfunction "1_1") (pintype "passive"))
      (node (ref "C61") (pin "1") (pinfunction "1_1") (pintype "passive"))
      (node (ref "C62") (pin "1") (pinfunction "1_1") (pintype "passive"))
      (node (ref "C63") (pin "1") (pinfunction "1_1") (pintype "passive"))
      (node (ref "IC2") (pin "4") (pinfunction "GND_4") (pintype "passive"))
      (node (ref "IC3") (pin "4") (pinfunction "AGND_4") (pintype "passive"))
      (node (ref "IC4") (pin "1") (pinfunction "AIN1N_1") (pintype "passive"))
      (node (ref "IC4") (pin "10") (pinfunction "AVSS_10") (pintype "passive"))
      (node (ref "IC4") (pin "11") (pinfunction "VNCP_11") (pintype "passive"))
      (node (ref "IC4") (pin "13") (pinfunction "REFN_13") (pintype "passive"))
      (node (ref "IC4") (pin "24") (pinfunction "NC_5_24") (pintype "passive"))
      (node (ref "IC4") (pin "27") (pinfunction "GND_27") (pintype "passive"))
      (node (ref "IC4") (pin "3") (pinfunction "AIN2N_3") (pintype "passive"))
      (node (ref "IC4") (pin "5") (pinfunction "NC_1_5") (pintype "passive"))
      (node (ref "IC4") (pin "6") (pinfunction "NC_2_6") (pintype "passive"))
      (node (ref "IC4") (pin "7") (pinfunction "NC_3_7") (pintype "passive"))
      (node (ref "IC4") (pin "8") (pinfunction "NC_4_8") (pintype "passive"))
      (node (ref "IC5") (pin "15") (pinfunction "EP_15") (pintype "passive"))
      (node (ref "IC5") (pin "7") (pinfunction "AGND_7") (pintype "passive"))
      (node (ref "IC6") (pin "4") (pinfunction "V-_4") (pintype "passive"))
      (node (ref "L9") (pin "2") (pinfunction "2_2") (pintype "passive"))
      (node (ref "R42") (pin "1") (pinfunction "1_1") (pintype "passive"))
      (node (ref "R43") (pin "1") (pinfunction "1_1") (pintype "passive"))
      (node (ref "R44") (pin "1") (pinfunction "1_1") (pintype "passive"))
      (node (ref "R46") (pin "1") (pinfunction "1_1") (pintype "passive"))
      (node (ref "R47") (pin "1") (pinfunction "1_1") (pintype "passive"))
      (node (ref "R49") (pin "1") (pinfunction "1_1") (pintype "passive"))
      (node (ref "R71") (pin "1") (pinfunction "1_1") (pintype "passive"))
      (node (ref "R72") (pin "1") (pinfunction "1_1") (pintype "passive"))
      (node (ref "R73") (pin "1") (pinfunction "1_1") (pintype "passive"))
      (node (ref "Y1") (pin "2") (pinfunction "GND_1_2") (pintype "passive"))
      (node (ref "Y1") (pin "4") (pinfunction "GND_2_4") (pintype "passive"))
    )
    (net (code "22") (name "Net-(C51-Pad2)") (class "Default")
      (node (ref "C51") (pin "2") (pinfunction "2_2") (pintype "passive"))
      (node (ref "R70") (pin "1") (pinfunction "1_1") (pintype "passive"))
    )
    (net (code "23") (name "Net-(IC2-VIN)") (class "Default")
      (node (ref "C34") (pin "2") (pinfunction "2_2") (pintype "passive"))
      (node (ref "C35") (pin "2") (pinfunction "2_2") (pintype "passive"))
      (node (ref "IC2") (pin "2") (pinfunction "VIN_2") (pintype "passive"))
      (node (ref "L6") (pin "1") (pinfunction "1_1") (pintype "passive"))
    )
    (net (code "24") (name "Net-(IC2-VOUT)") (class "Default")
      (node (ref "C33") (pin "2") (pinfunction "2_2") (pintype "passive"))
      (node (ref "IC2") (pin "6") (pinfunction "VOUT_6") (pintype "passive"))
      (node (ref "L5") (pin "1") (pinfunction "1_1") (pintype "passive"))
    )
    (net (code "25") (name "Net-(IC3-VDD)") (class "Default")
      (node (ref "C36") (pin "2") (pinfunction "2_2") (pintype "passive"))
      (node (ref "C37") (pin "1") (pinfunction "1_1") (pintype "passive"))
      (node (ref "IC3") (pin "1") (pinfunction "VDD_1") (pintype "passive"))
      (node (ref "L7") (pin "1") (pinfunction "1_1") (pintype "passive"))
      (node (ref "TP23") (pin "1") (pinfunction "TP_1") (pintype "passive"))
    )
    (net (code "26") (name "Net-(IC3-VOUT)") (class "Default")
      (node (ref "IC3") (pin "2") (pinfunction "VOUT_2") (pintype "passive"))
      (node (ref "R50") (pin "2") (pinfunction "2_2") (pintype "passive"))
      (node (ref "TP26") (pin "1") (pinfunction "TP_1") (pintype "passive"))
    )
    (net (code "27") (name "Net-(IC3-VREFIO)") (class "Default")
      (node (ref "C31") (pin "2") (pinfunction "2_2") (pintype "passive"))
      (node (ref "C32") (pin "1") (pinfunction "1_1") (pintype "passive"))
      (node (ref "IC3") (pin "10") (pinfunction "VREFIO_10") (pintype "passive"))
      (node (ref "R74") (pin "2") (pinfunction "2_2") (pintype "passive"))
    )
    (net (code "28") (name "Net-(IC4-AIN1P)") (class "Default")
      (node (ref "C46") (pin "2") (pinfunction "2_2") (pintype "passive"))
      (node (ref "IC4") (pin "2") (pinfunction "AIN1P_2") (pintype "passive"))
      (node (ref "R61") (pin "2") (pinfunction "2_2") (pintype "passive"))
      (node (ref "TP27") (pin "1") (pinfunction "TP_1") (pintype "passive"))
    )
    (net (code "29") (name "Net-(IC4-AIN2P)") (class "Default")
      (node (ref "C52") (pin "2") (pinfunction "2_2") (pintype "passive"))
      (node (ref "IC4") (pin "4") (pinfunction "AIN2P_4") (pintype "passive"))
      (node (ref "R60") (pin "2") (pinfunction "2_2") (pintype "passive"))
      (node (ref "TP32") (pin "1") (pinfunction "TP_1") (pintype "passive"))
    )
    (net (code "30") (name "Net-(IC4-AVDD)") (class "Default")
      (node (ref "C59") (pin "2") (pinfunction "2_2") (pintype "passive"))
      (node (ref "C60") (pin "2") (pinfunction "2_2") (pintype "passive"))
      (node (ref "IC4") (pin "9") (pinfunction "AVDD_9") (pintype "passive"))
      (node (ref "L11") (pin "1") (pinfunction "1_1") (pintype "passive"))
      (node (ref "R81") (pin "2") (pinfunction "2_2") (pintype "passive"))
    )
    (net (code "31") (name "Net-(IC4-CAP)") (class "Default")
      (node (ref "C38") (pin "1") (pinfunction "1_1") (pintype "passive"))
      (node (ref "IC4") (pin "28") (pinfunction "CAP_28") (pintype "passive"))
    )
    (net (code "32") (name "Net-(IC4-IOVDD_1)") (class "Default")
      (node (ref "C62") (pin "2") (pinfunction "2_2") (pintype "passive"))
      (node (ref "C63") (pin "2") (pinfunction "2_2") (pintype "passive"))
      (node (ref "IC4") (pin "15") (pinfunction "IOVDD_1_15") (pintype "passive"))
      (node (ref "IC4") (pin "16") (pinfunction "RESV_16") (pintype "passive"))
      (node (ref "L12") (pin "2") (pinfunction "2_2") (pintype "passive"))
      (node (ref "TP35") (pin "1") (pinfunction "TP_1") (pintype "passive"))
    )
    (net (code "33") (name "Net-(IC4-M0)") (class "Default")
      (node (ref "IC4") (pin "30") (pinfunction "M0_30") (pintype "passive"))
      (node (ref "R40") (pin "1") (pinfunction "1_1") (pintype "passive"))
      (node (ref "R44") (pin "2") (pinfunction "2_2") (pintype "passive"))
    )
    (net (code "34") (name "Net-(IC4-M1)") (class "Default")
      (node (ref "IC4") (pin "31") (pinfunction "M1_31") (pintype "passive"))
      (node (ref "R39") (pin "1") (pinfunction "1_1") (pintype "passive"))
      (node (ref "R43") (pin "2") (pinfunction "2_2") (pintype "passive"))
    )
    (net (code "35") (name "Net-(IC4-M2)") (class "Default")
      (node (ref "IC4") (pin "32") (pinfunction "M2_32") (pintype "passive"))
      (node (ref "R41") (pin "1") (pinfunction "1_1") (pintype "passive"))
      (node (ref "R42") (pin "2") (pinfunction "2_2") (pintype "passive"))
    )
    (net (code "36") (name "Net-(IC4-REFEXT)") (class "Default")
      (node (ref "C55") (pin "2") (pinfunction "2_2") (pintype "passive"))
      (node (ref "IC4") (pin "14") (pinfunction "REFEXT_14") (pintype "passive"))
      (node (ref "R75") (pin "1") (pinfunction "1_1") (pintype "passive"))
      (node (ref "R81") (pin "1") (pinfunction "1_1") (pintype "passive"))
    )
    (net (code "37") (name "Net-(IC4-REFP)") (class "Default")
      (node (ref "C61") (pin "2") (pinfunction "2_2") (pintype "passive"))
      (node (ref "IC4") (pin "12") (pinfunction "REFP_12") (pintype "passive"))
    )
    (net (code "38") (name "Net-(IC4-XTAL1{slash}CLKIN)") (class "Default")
      (node (ref "C40") (pin "2") (pinfunction "2_2") (pintype "passive"))
      (node (ref "IC4") (pin "25") (pinfunction "XTAL1/CLKIN_25") (pintype "passive"))
      (node (ref "TP24") (pin "1") (pinfunction "TP_1") (pintype "passive"))
      (node (ref "Y1") (pin "1") (pinfunction "CRYSTAL_1_1") (pintype "passive"))
    )
    (net (code "39") (name "Net-(IC4-XTAL2)") (class "Default")
      (node (ref "C39") (pin "2") (pinfunction "2_2") (pintype "passive"))
      (node (ref "IC4") (pin "26") (pinfunction "XTAL2_26") (pintype "passive"))
      (node (ref "Y1") (pin "3") (pinfunction "CRYSTAL_2_3") (pintype "passive"))
    )
    (net (code "40") (name "Net-(IC5-C1)") (class "Default")
      (node (ref "C57") (pin "1") (pinfunction "1_1") (pintype "passive"))
      (node (ref "IC5") (pin "10") (pinfunction "C1_10") (pintype "passive"))
      (node (ref "R61") (pin "1") (pinfunction "1_1") (pintype "passive"))
      (node (ref "R83") (pin "2") (pinfunction "2_2") (pintype "passive"))
      (node (ref "TP29") (pin "1") (pinfunction "TP_1") (pintype "passive"))
    )
    (net (code "41") (name "Net-(IC5-C2)") (class "Default")
      (node (ref "C57") (pin "2") (pinfunction "2_2") (pintype "passive"))
      (node (ref "IC5") (pin "9") (pinfunction "C2_9") (pintype "passive"))
      (node (ref "R67") (pin "2") (pinfunction "2_2") (pintype "passive"))
      (node (ref "R83") (pin "1") (pinfunction "1_1") (pintype "passive"))
      (node (ref "TP31") (pin "1") (pinfunction "TP_1") (pintype "passive"))
    )
    (net (code "42") (name "Net-(IC5-DGND)") (class "Default")
      (node (ref "IC5") (pin "1") (pinfunction "DGND_1") (pintype "passive"))
      (node (ref "L9") (pin "1") (pinfunction "1_1") (pintype "passive"))
    )
    (net (code "43") (name "Net-(IC5-MENB)") (class "Default")
      (node (ref "IC5") (pin "2") (pinfunction "MENB_2") (pintype "passive"))
      (node (ref "R59") (pin "1") (pinfunction "1_1") (pintype "passive"))
    )
    (net (code "44") (name "Net-(IC5-RE)") (class "Default")
      (node (ref "IC5") (pin "13") (pinfunction "RE_13") (pintype "passive"))
      (node (ref "IC6") (pin "1") (pinfunction "OUTPUT_A_1") (pintype "passive"))
      (node (ref "IC6") (pin "2") (pinfunction "INVERTING_INPUT_A_2") (pintype "passive"))
      (node (ref "R65") (pin "2") (pinfunction "2_2") (pintype "passive"))
    )
    (net (code "45") (name "Net-(IC5-SCL)") (class "Default")
      (node (ref "IC5") (pin "3") (pinfunction "SCL_3") (pintype "passive"))
      (node (ref "R62") (pin "1") (pinfunction "1_1") (pintype "passive"))
    )
    (net (code "46") (name "Net-(IC5-SDA)") (class "Default")
      (node (ref "IC5") (pin "4") (pinfunction "SDA_4") (pintype "passive"))
      (node (ref "R64") (pin "1") (pinfunction "1_1") (pintype "passive"))
    )
    (net (code "47") (name "Net-(IC5-VDD)") (class "Default")
      (node (ref "C53") (pin "1") (pinfunction "1_1") (pintype "passive"))
      (node (ref "C56") (pin "2") (pinfunction "2_2") (pintype "passive"))
      (node (ref "IC5") (pin "6") (pinfunction "VDD_6") (pintype "passive"))
      (node (ref "L13") (pin "2") (pinfunction "2_2") (pintype "passive"))
      (node (ref "TP33") (pin "1") (pinfunction "TP_1") (pintype "passive"))
    )
    (net (code "48") (name "Net-(IC5-VOUT)") (class "Default")
      (node (ref "IC5") (pin "8") (pinfunction "VOUT_8") (pintype "passive"))
      (node (ref "R68") (pin "2") (pinfunction "2_2") (pintype "passive"))
      (node (ref "TP34") (pin "1") (pinfunction "TP_1") (pintype "passive"))
    )
    (net (code "49") (name "Net-(IC5-VREF)") (class "Default")
      (node (ref "C47") (pin "2") (pinfunction "2_2") (pintype "passive"))
      (node (ref "IC5") (pin "11") (pinfunction "VREF_11") (pintype "passive"))
      (node (ref "R38") (pin "1") (pinfunction "1_1") (pintype "passive"))
      (node (ref "R48") (pin "1") (pinfunction "1_1") (pintype "passive"))
      (node (ref "R50") (pin "1") (pinfunction "1_1") (pintype "passive"))
    )
    (net (code "50") (name "Net-(IC5-WE)") (class "Default")
      (node (ref "IC5") (pin "12") (pinfunction "WE_12") (pintype "passive"))
      (node (ref "IC6") (pin "6") (pinfunction "INVERTING_INPUT_B_6") (pintype "passive"))
      (node (ref "IC6") (pin "7") (pinfunction "OUTPUT_B_7") (pintype "passive"))
      (node (ref "R63") (pin "2") (pinfunction "2_2") (pintype "passive"))
    )
    (net (code "51") (name "Net-(IC6-V+)") (class "Default")
      (node (ref "C44") (pin "2") (pinfunction "2_2") (pintype "passive"))
      (node (ref "C45") (pin "1") (pinfunction "1_1") (pintype "passive"))
      (node (ref "IC6") (pin "8") (pinfunction "V+_8") (pintype "passive"))
      (node (ref "L10") (pin "2") (pinfunction "2_2") (pintype "passive"))
    )
    (net (code "52") (name "Net-(R60-Pad1)") (class "Default")
      (node (ref "R60") (pin "1") (pinfunction "1_1") (pintype "passive"))
      (node (ref "R67") (pin "1") (pinfunction "1_1") (pintype "passive"))
      (node (ref "R68") (pin "1") (pinfunction "1_1") (pintype "passive"))
    )
    (net (code "53") (name "Net-(TP25-TP)") (class "Default")
      (node (ref "C41") (pin "1") (pinfunction "1_1") (pintype "passive"))
      (node (ref "C43") (pin "2") (pinfunction "2_2") (pintype "passive"))
      (node (ref "L8") (pin "1") (pinfunction "1_1") (pintype "passive"))
      (node (ref "R51") (pin "2") (pinfunction "2_2") (pintype "passive"))
      (node (ref "R52") (pin "2") (pinfunction "2_2") (pintype "passive"))
      (node (ref "R53") (pin "2") (pinfunction "2_2") (pintype "passive"))
      (node (ref "R55") (pin "2") (pinfunction "2_2") (pintype "passive"))
      (node (ref "R56") (pin "2") (pinfunction "2_2") (pintype "passive"))
      (node (ref "R57") (pin "2") (pinfunction "2_2") (pintype "passive"))
      (node (ref "R58") (pin "2") (pinfunction "2_2") (pintype "passive"))
      (node (ref "TP25") (pin "1") (pinfunction "TP_1") (pintype "passive"))
    )
    (net (code "54") (name "unconnected-(IC2-DNC_1-Pad1)") (class "Default")
      (node (ref "IC2") (pin "1") (pinfunction "DNC_1_1") (pintype "passive"))
    )
    (net (code "55") (name "unconnected-(IC2-DNC_2-Pad8)") (class "Default")
      (node (ref "IC2") (pin "8") (pinfunction "DNC_2_8") (pintype "passive"))
    )
    (net (code "56") (name "unconnected-(IC2-NC-Pad7)") (class "Default")
      (node (ref "IC2") (pin "7") (pinfunction "NC_7") (pintype "passive"))
    )
    (net (code "57") (name "unconnected-(IC2-TEMP-Pad3)") (class "Default")
      (node (ref "IC2") (pin "3") (pinfunction "TEMP_3") (pintype "passive"))
    )
    (net (code "58") (name "unconnected-(IC2-TRIM{slash}NR-Pad5)") (class "Default")
      (node (ref "IC2") (pin "5") (pinfunction "TRIM/NR_5") (pintype "passive"))
    )
    (net (code "59") (name "unconnected-(IC3-NC_1-Pad3)") (class "Default")
      (node (ref "IC3") (pin "3") (pinfunction "NC_1_3") (pintype "passive"))
    )
    (net (code "60") (name "unconnected-(IC3-NC_2-Pad9)") (class "Default")
      (node (ref "IC3") (pin "9") (pinfunction "NC_2_9") (pintype "passive"))
    )
    (net (code "61") (name "unconnected-(IC5-NC-Pad5)") (class "Default")
      (node (ref "IC5") (pin "5") (pinfunction "NC_5") (pintype "passive"))
    )
  )
)
